# T35_1_IO.net
KiCad netlist of a schematic drawn in Altium Designer
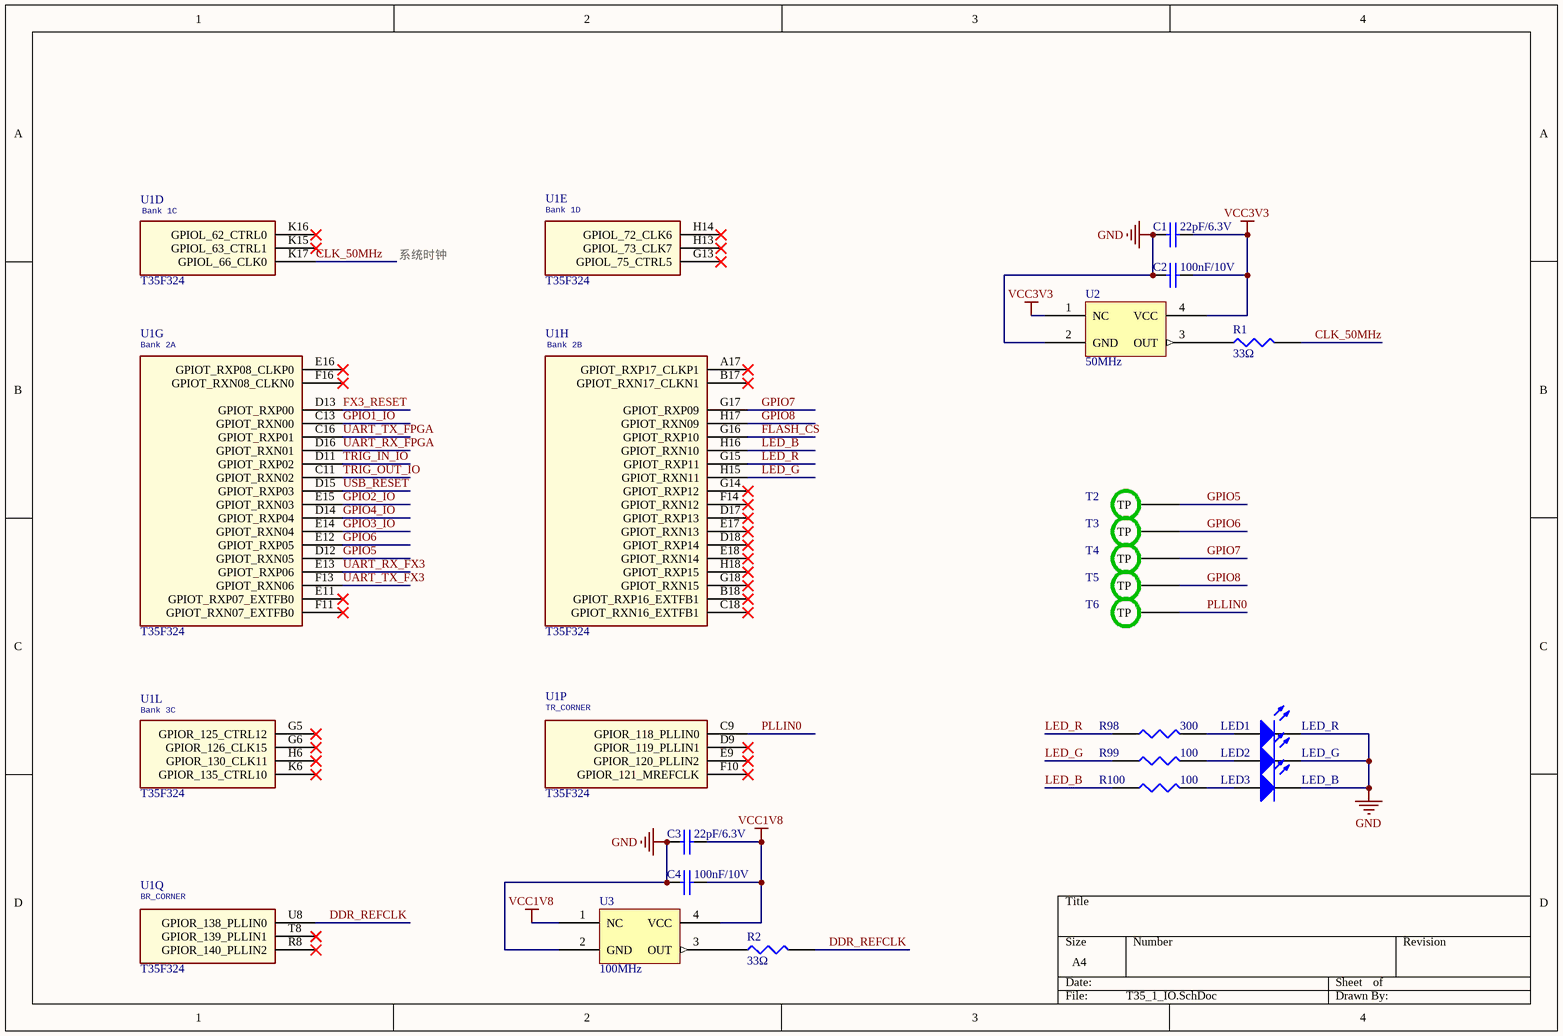
[diagram p0: T35_1_IO.SchDoc]

(export (version "E")
  (design (tool "Eeschema 10.0.6"))
  (components
    (comp (ref "C1")
      (value "22pF/6.3V")
      (footprint "0201CS")
      (description "贴片电容")
      (libsource (lib "*") (part "CAP"))
    )
    (comp (ref "C2")
      (value "100nF/10V")
      (footprint "0201CS")
      (description "贴片电容")
      (libsource (lib "*") (part "CAP"))
    )
    (comp (ref "C3")
      (value "22pF/6.3V")
      (footprint "0201CS")
      (description "贴片电容")
      (libsource (lib "*") (part "CAP"))
    )
    (comp (ref "C4")
      (value "100nF/10V")
      (footprint "0201CS")
      (description "贴片电容")
      (libsource (lib "*") (part "CAP"))
    )
    (comp (ref "LED1")
      (value "LED_R")
      (footprint "0402LED")
      (description "红色LED")
      (fields (field (name "PUBLISHER") "Altium Limited"))
      (libsource (lib "QHY_SCHLIB") (part "LED1"))
    )
    (comp (ref "LED2")
      (value "LED_G")
      (footprint "0402LED")
      (description "绿色LED")
      (fields (field (name "PUBLISHER") "Altium Limited"))
      (libsource (lib "QHY_SCHLIB") (part "LED1"))
    )
    (comp (ref "LED3")
      (value "LED_B")
      (footprint "0402LED")
      (description "蓝色LED")
      (fields (field (name "PUBLISHER") "Altium Limited"))
      (libsource (lib "QHY_SCHLIB") (part "LED1"))
    )
    (comp (ref "R1")
      (value "33Ω")
      (footprint "0402RS")
      (description "贴片电阻")
      (libsource (lib "*") (part "RES1"))
    )
    (comp (ref "R2")
      (value "33Ω")
      (footprint "0402RS")
      (description "贴片电阻")
      (libsource (lib "*") (part "RES1"))
    )
    (comp (ref "R98")
      (value "300")
      (footprint "0201RS")
      (description "贴片电阻")
      (libsource (lib "*") (part "RES1"))
    )
    (comp (ref "R99")
      (value "100")
      (footprint "0201RS")
      (description "贴片电阻")
      (libsource (lib "*") (part "RES1"))
    )
    (comp (ref "R100")
      (value "100")
      (footprint "0201RS")
      (description "贴片电阻")
      (libsource (lib "*") (part "RES1"))
    )
    (comp (ref "T2")
      (value "~")
      (footprint "TP-S")
      (description "测试点")
      (libsource (lib "QHY_SCHLIB") (part "TP"))
    )
    (comp (ref "T3")
      (value "~")
      (footprint "TP-S")
      (description "测试点")
      (libsource (lib "QHY_SCHLIB") (part "TP"))
    )
    (comp (ref "T4")
      (value "~")
      (footprint "TP-S")
      (description "测试点")
      (libsource (lib "QHY_SCHLIB") (part "TP"))
    )
    (comp (ref "T5")
      (value "~")
      (footprint "TP-S")
      (description "测试点")
      (libsource (lib "QHY_SCHLIB") (part "TP"))
    )
    (comp (ref "T6")
      (value "~")
      (footprint "TP-S")
      (description "测试点")
      (libsource (lib "QHY_SCHLIB") (part "TP"))
    )
    (comp (ref "U1")
      (value "T35F324")
      (footprint "T35-F324-BGA100P9X9-81A")
      (description "FPGA芯片")
      (libsource (lib "orcadt35-v1.0_Library") (part "T35F324"))
    )
    (comp (ref "U2")
      (value "50MHz")
      (footprint "XTAL_SMD_SMALL")
      (description "贴片有源晶振")
      (libsource (lib "*") (part "24LC00"))
    )
    (comp (ref "U3")
      (value "100MHz")
      (footprint "XTAL_SMD_SMALL")
      (description "贴片有源晶振")
      (libsource (lib "*") (part "24LC00"))
    )
  )
  (nets
    (net (code "1") (name "/CLK_50MHz") (class "Default")
      (node (ref "R1") (pin "2") (pinfunction "2_2") (pintype "passive"))
      (node (ref "U1") (pin "K17") (pinfunction "GPIOL_66_CLK0_K17") (pintype "passive"))
    )
    (net (code "2") (name "/DDR_REFCLK") (class "Default")
      (node (ref "R2") (pin "2") (pinfunction "2_2") (pintype "passive"))
      (node (ref "U1") (pin "U8") (pinfunction "GPIOR_138_PLLIN0_U8") (pintype "power_in"))
    )
    (net (code "3") (name "/FLASH_CS") (class "Default")
      (node (ref "U1") (pin "G16") (pinfunction "GPIOT_RXP10_G16") (pintype "passive"))
    )
    (net (code "4") (name "/FX3_RESET") (class "Default")
      (node (ref "U1") (pin "D13") (pinfunction "GPIOT_RXP00_D13") (pintype "passive"))
    )
    (net (code "5") (name "/GPIO1_IO") (class "Default")
      (node (ref "U1") (pin "C13") (pinfunction "GPIOT_RXN00_C13") (pintype "passive"))
    )
    (net (code "6") (name "/GPIO2_IO") (class "Default")
      (node (ref "U1") (pin "E15") (pinfunction "GPIOT_RXN03_E15") (pintype "passive"))
    )
    (net (code "7") (name "/GPIO3_IO") (class "Default")
      (node (ref "U1") (pin "E14") (pinfunction "GPIOT_RXN04_E14") (pintype "passive"))
    )
    (net (code "8") (name "/GPIO4_IO") (class "Default")
      (node (ref "U1") (pin "D14") (pinfunction "GPIOT_RXP04_D14") (pintype "passive"))
    )
    (net (code "9") (name "/GPIO5") (class "Default")
      (node (ref "T2") (pin "1") (pinfunction "TP_1") (pintype "passive"))
      (node (ref "U1") (pin "D12") (pinfunction "GPIOT_RXN05_D12") (pintype "passive"))
    )
    (net (code "10") (name "/GPIO6") (class "Default")
      (node (ref "T3") (pin "1") (pinfunction "TP_1") (pintype "passive"))
      (node (ref "U1") (pin "E12") (pinfunction "GPIOT_RXP05_E12") (pintype "passive"))
    )
    (net (code "11") (name "/GPIO7") (class "Default")
      (node (ref "T4") (pin "1") (pinfunction "TP_1") (pintype "passive"))
      (node (ref "U1") (pin "G17") (pinfunction "GPIOT_RXP09_G17") (pintype "passive"))
    )
    (net (code "12") (name "/GPIO8") (class "Default")
      (node (ref "T5") (pin "1") (pinfunction "TP_1") (pintype "passive"))
      (node (ref "U1") (pin "H17") (pinfunction "GPIOT_RXN09_H17") (pintype "passive"))
    )
    (net (code "13") (name "/LED_B") (class "Default")
      (node (ref "R100") (pin "1") (pinfunction "1_1") (pintype "passive"))
      (node (ref "U1") (pin "H16") (pinfunction "GPIOT_RXN10_H16") (pintype "passive"))
    )
    (net (code "14") (name "/LED_G") (class "Default")
      (node (ref "R99") (pin "1") (pinfunction "1_1") (pintype "passive"))
      (node (ref "U1") (pin "H15") (pinfunction "GPIOT_RXN11_H15") (pintype "passive"))
    )
    (net (code "15") (name "/LED_R") (class "Default")
      (node (ref "R98") (pin "1") (pinfunction "1_1") (pintype "passive"))
      (node (ref "U1") (pin "G15") (pinfunction "GPIOT_RXP11_G15") (pintype "passive"))
    )
    (net (code "16") (name "/PLLIN0") (class "Default")
      (node (ref "T6") (pin "1") (pinfunction "TP_1") (pintype "passive"))
      (node (ref "U1") (pin "C9") (pinfunction "GPIOR_118_PLLIN0_C9") (pintype "power_in"))
    )
    (net (code "17") (name "/TRIG_IN_IO") (class "Default")
      (node (ref "U1") (pin "D11") (pinfunction "GPIOT_RXP02_D11") (pintype "passive"))
    )
    (net (code "18") (name "/TRIG_OUT_IO") (class "Default")
      (node (ref "U1") (pin "C11") (pinfunction "GPIOT_RXN02_C11") (pintype "passive"))
    )
    (net (code "19") (name "/UART_RX_FPGA") (class "Default")
      (node (ref "U1") (pin "D16") (pinfunction "GPIOT_RXN01_D16") (pintype "passive"))
    )
    (net (code "20") (name "/UART_RX_FX3") (class "Default")
      (node (ref "U1") (pin "E13") (pinfunction "GPIOT_RXP06_E13") (pintype "passive"))
    )
    (net (code "21") (name "/UART_TX_FPGA") (class "Default")
      (node (ref "U1") (pin "C16") (pinfunction "GPIOT_RXP01_C16") (pintype "passive"))
    )
    (net (code "22") (name "/UART_TX_FX3") (class "Default")
      (node (ref "U1") (pin "F13") (pinfunction "GPIOT_RXN06_F13") (pintype "passive"))
    )
    (net (code "23") (name "/USB_RESET") (class "Default")
      (node (ref "U1") (pin "D15") (pinfunction "GPIOT_RXP03_D15") (pintype "passive"))
    )
    (net (code "24") (name "GND") (class "Default")
      (node (ref "C1") (pin "1") (pinfunction "1_1") (pintype "passive"))
      (node (ref "C2") (pin "2") (pinfunction "2_2") (pintype "passive"))
      (node (ref "C3") (pin "1") (pinfunction "1_1") (pintype "passive"))
      (node (ref "C4") (pin "2") (pinfunction "2_2") (pintype "passive"))
      (node (ref "LED1") (pin "2") (pinfunction "K_2") (pintype "passive"))
      (node (ref "LED2") (pin "2") (pinfunction "K_2") (pintype "passive"))
      (node (ref "LED3") (pin "2") (pinfunction "K_2") (pintype "passive"))
      (node (ref "U2") (pin "2") (pinfunction "GND_2") (pintype "power_in"))
      (node (ref "U3") (pin "2") (pinfunction "GND_2") (pintype "power_in"))
    )
    (net (code "25") (name "Net-(LED1-A)") (class "Default")
      (node (ref "LED1") (pin "1") (pinfunction "A_1") (pintype "passive"))
      (node (ref "R98") (pin "2") (pinfunction "2_2") (pintype "passive"))
    )
    (net (code "26") (name "Net-(LED2-A)") (class "Default")
      (node (ref "LED2") (pin "1") (pinfunction "A_1") (pintype "passive"))
      (node (ref "R99") (pin "2") (pinfunction "2_2") (pintype "passive"))
    )
    (net (code "27") (name "Net-(LED3-A)") (class "Default")
      (node (ref "LED3") (pin "1") (pinfunction "A_1") (pintype "passive"))
      (node (ref "R100") (pin "2") (pinfunction "2_2") (pintype "passive"))
    )
    (net (code "28") (name "Net-(U2-OUT)") (class "Default")
      (node (ref "R1") (pin "1") (pinfunction "1_1") (pintype "passive"))
      (node (ref "U2") (pin "3") (pinfunction "OUT_3") (pintype "output"))
    )
    (net (code "29") (name "Net-(U3-OUT)") (class "Default")
      (node (ref "R2") (pin "1") (pinfunction "1_1") (pintype "passive"))
      (node (ref "U3") (pin "3") (pinfunction "OUT_3") (pintype "output"))
    )
    (net (code "30") (name "VCC1V8") (class "Default")
      (node (ref "C3") (pin "2") (pinfunction "2_2") (pintype "passive"))
      (node (ref "C4") (pin "1") (pinfunction "1_1") (pintype "passive"))
      (node (ref "U3") (pin "1") (pinfunction "NC_1") (pintype "passive"))
      (node (ref "U3") (pin "4") (pinfunction "VCC_4") (pintype "power_in"))
    )
    (net (code "31") (name "VCC3V3") (class "Default")
      (node (ref "C1") (pin "2") (pinfunction "2_2") (pintype "passive"))
      (node (ref "C2") (pin "1") (pinfunction "1_1") (pintype "passive"))
      (node (ref "U2") (pin "1") (pinfunction "NC_1") (pintype "passive"))
      (node (ref "U2") (pin "4") (pinfunction "VCC_4") (pintype "power_in"))
    )
    (net (code "32") (name "unconnected-(U1D-GPIOL_62_CTRL0-PadK16)") (class "Default")
      (node (ref "U1") (pin "K16") (pinfunction "GPIOL_62_CTRL0_K16") (pintype "passive+no_connect"))
    )
    (net (code "33") (name "unconnected-(U1D-GPIOL_63_CTRL1-PadK15)") (class "Default")
      (node (ref "U1") (pin "K15") (pinfunction "GPIOL_63_CTRL1_K15") (pintype "passive+no_connect"))
    )
    (net (code "34") (name "unconnected-(U1E-GPIOL_72_CLK6-PadH14)") (class "Default")
      (node (ref "U1") (pin "H14") (pinfunction "GPIOL_72_CLK6_H14") (pintype "passive+no_connect"))
    )
    (net (code "35") (name "unconnected-(U1E-GPIOL_73_CLK7-PadH13)") (class "Default")
      (node (ref "U1") (pin "H13") (pinfunction "GPIOL_73_CLK7_H13") (pintype "passive+no_connect"))
    )
    (net (code "36") (name "unconnected-(U1E-GPIOL_75_CTRL5-PadG13)") (class "Default")
      (node (ref "U1") (pin "G13") (pinfunction "GPIOL_75_CTRL5_G13") (pintype "passive+no_connect"))
    )
    (net (code "37") (name "unconnected-(U1G-GPIOT_RXN07_EXTFB0-PadF11)") (class "Default")
      (node (ref "U1") (pin "F11") (pinfunction "GPIOT_RXN07_EXTFB0_F11") (pintype "passive+no_connect"))
    )
    (net (code "38") (name "unconnected-(U1G-GPIOT_RXN08_CLKN0-PadF16)") (class "Default")
      (node (ref "U1") (pin "F16") (pinfunction "GPIOT_RXN08_CLKN0_F16") (pintype "passive+no_connect"))
    )
    (net (code "39") (name "unconnected-(U1G-GPIOT_RXP07_EXTFB0-PadE11)") (class "Default")
      (node (ref "U1") (pin "E11") (pinfunction "GPIOT_RXP07_EXTFB0_E11") (pintype "passive+no_connect"))
    )
    (net (code "40") (name "unconnected-(U1G-GPIOT_RXP08_CLKP0-PadE16)") (class "Default")
      (node (ref "U1") (pin "E16") (pinfunction "GPIOT_RXP08_CLKP0_E16") (pintype "passive+no_connect"))
    )
    (net (code "41") (name "unconnected-(U1H-GPIOT_RXN12-PadF14)") (class "Default")
      (node (ref "U1") (pin "F14") (pinfunction "GPIOT_RXN12_F14") (pintype "passive+no_connect"))
    )
    (net (code "42") (name "unconnected-(U1H-GPIOT_RXN13-PadE17)") (class "Default")
      (node (ref "U1") (pin "E17") (pinfunction "GPIOT_RXN13_E17") (pintype "passive+no_connect"))
    )
    (net (code "43") (name "unconnected-(U1H-GPIOT_RXN14-PadE18)") (class "Default")
      (node (ref "U1") (pin "E18") (pinfunction "GPIOT_RXN14_E18") (pintype "passive+no_connect"))
    )
    (net (code "44") (name "unconnected-(U1H-GPIOT_RXN15-PadG18)") (class "Default")
      (node (ref "U1") (pin "G18") (pinfunction "GPIOT_RXN15_G18") (pintype "passive+no_connect"))
    )
    (net (code "45") (name "unconnected-(U1H-GPIOT_RXN16_EXTFB1-PadC18)") (class "Default")
      (node (ref "U1") (pin "C18") (pinfunction "GPIOT_RXN16_EXTFB1_C18") (pintype "passive+no_connect"))
    )
    (net (code "46") (name "unconnected-(U1H-GPIOT_RXN17_CLKN1-PadB17)") (class "Default")
      (node (ref "U1") (pin "B17") (pinfunction "GPIOT_RXN17_CLKN1_B17") (pintype "passive+no_connect"))
    )
    (net (code "47") (name "unconnected-(U1H-GPIOT_RXP12-PadG14)") (class "Default")
      (node (ref "U1") (pin "G14") (pinfunction "GPIOT_RXP12_G14") (pintype "passive+no_connect"))
    )
    (net (code "48") (name "unconnected-(U1H-GPIOT_RXP13-PadD17)") (class "Default")
      (node (ref "U1") (pin "D17") (pinfunction "GPIOT_RXP13_D17") (pintype "passive+no_connect"))
    )
    (net (code "49") (name "unconnected-(U1H-GPIOT_RXP14-PadD18)") (class "Default")
      (node (ref "U1") (pin "D18") (pinfunction "GPIOT_RXP14_D18") (pintype "passive+no_connect"))
    )
    (net (code "50") (name "unconnected-(U1H-GPIOT_RXP15-PadH18)") (class "Default")
      (node (ref "U1") (pin "H18") (pinfunction "GPIOT_RXP15_H18") (pintype "passive+no_connect"))
    )
    (net (code "51") (name "unconnected-(U1H-GPIOT_RXP16_EXTFB1-PadB18)") (class "Default")
      (node (ref "U1") (pin "B18") (pinfunction "GPIOT_RXP16_EXTFB1_B18") (pintype "passive+no_connect"))
    )
    (net (code "52") (name "unconnected-(U1H-GPIOT_RXP17_CLKP1-PadA17)") (class "Default")
      (node (ref "U1") (pin "A17") (pinfunction "GPIOT_RXP17_CLKP1_A17") (pintype "passive+no_connect"))
    )
    (net (code "53") (name "unconnected-(U1L-GPIOR_125_CTRL12-PadG5)") (class "Default")
      (node (ref "U1") (pin "G5") (pinfunction "GPIOR_125_CTRL12_G5") (pintype "passive+no_connect"))
    )
    (net (code "54") (name "unconnected-(U1L-GPIOR_126_CLK15-PadG6)") (class "Default")
      (node (ref "U1") (pin "G6") (pinfunction "GPIOR_126_CLK15_G6") (pintype "passive+no_connect"))
    )
    (net (code "55") (name "unconnected-(U1L-GPIOR_130_CLK11-PadH6)") (class "Default")
      (node (ref "U1") (pin "H6") (pinfunction "GPIOR_130_CLK11_H6") (pintype "passive+no_connect"))
    )
    (net (code "56") (name "unconnected-(U1L-GPIOR_135_CTRL10-PadK6)") (class "Default")
      (node (ref "U1") (pin "K6") (pinfunction "GPIOR_135_CTRL10_K6") (pintype "passive+no_connect"))
    )
    (net (code "57") (name "unconnected-(U1P-GPIOR_119_PLLIN1-PadD9)") (class "Default")
      (node (ref "U1") (pin "D9") (pinfunction "GPIOR_119_PLLIN1_D9") (pintype "power_in+no_connect"))
    )
    (net (code "58") (name "unconnected-(U1P-GPIOR_120_PLLIN2-PadE9)") (class "Default")
      (node (ref "U1") (pin "E9") (pinfunction "GPIOR_120_PLLIN2_E9") (pintype "power_in+no_connect"))
    )
    (net (code "59") (name "unconnected-(U1P-GPIOR_121_MREFCLK-PadF10)") (class "Default")
      (node (ref "U1") (pin "F10") (pinfunction "GPIOR_121_MREFCLK_F10") (pintype "power_in+no_connect"))
    )
    (net (code "60") (name "unconnected-(U1Q-GPIOR_139_PLLIN1-PadT8)") (class "Default")
      (node (ref "U1") (pin "T8") (pinfunction "GPIOR_139_PLLIN1_T8") (pintype "power_in+no_connect"))
    )
    (net (code "61") (name "unconnected-(U1Q-GPIOR_140_PLLIN2-PadR8)") (class "Default")
      (node (ref "U1") (pin "R8") (pinfunction "GPIOR_140_PLLIN2_R8") (pintype "power_in+no_connect"))
    )
  )
)
